# Sheet1.net
KiCad netlist of a schematic drawn in Altium Designer
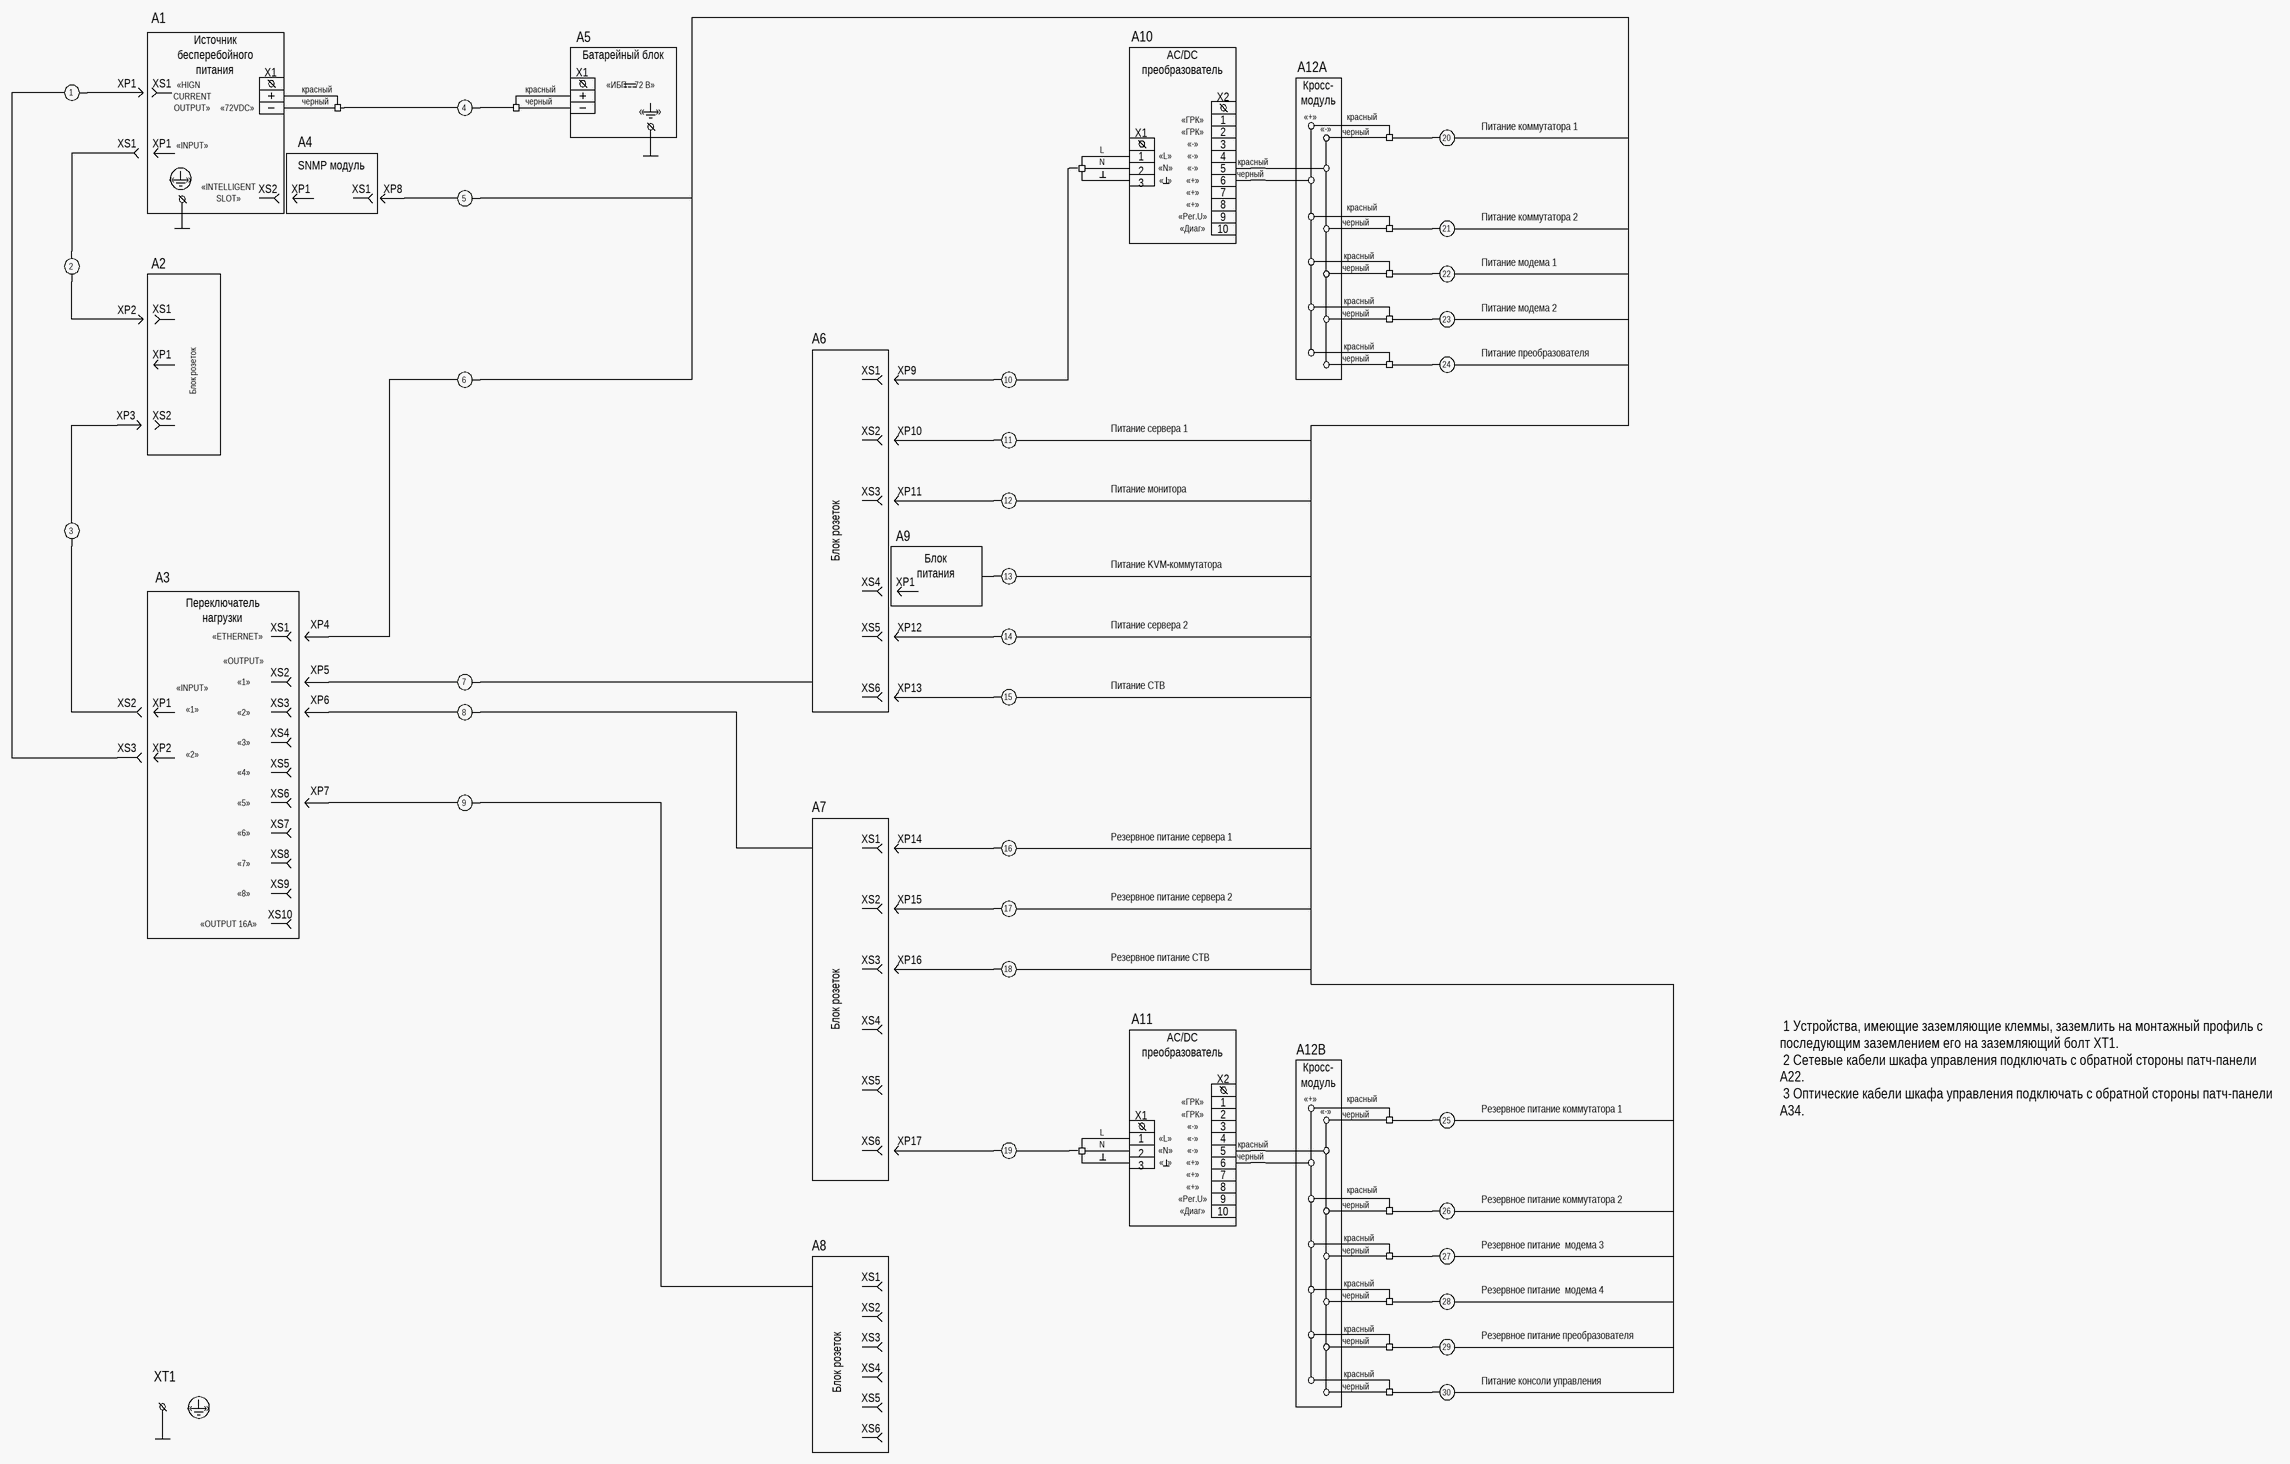
[diagram p0: Sheet1.SchDoc]

(export (version "E")
  (design (tool "Eeschema 10.0.6"))
  (components
    (comp (ref "1") (value "CABLE") (libsource (lib "RSP2STLIB") (part "CABLE")))
    (comp (ref "2") (value "CABLE") (libsource (lib "RSP2STLIB") (part "CABLE")))
    (comp (ref "3") (value "CABLE") (libsource (lib "RSP2STLIB") (part "CABLE")))
    (comp (ref "4") (value "CABLE") (libsource (lib "RSP2STLIB") (part "CABLE")))
    (comp (ref "5") (value "CABLE") (libsource (lib "RSP2STLIB") (part "CABLE")))
    (comp (ref "6") (value "CABLE") (libsource (lib "RSP2STLIB") (part "CABLE")))
    (comp (ref "7") (value "CABLE") (libsource (lib "RSP2STLIB") (part "CABLE")))
    (comp (ref "8") (value "CABLE") (libsource (lib "RSP2STLIB") (part "CABLE")))
    (comp (ref "9") (value "CABLE") (libsource (lib "RSP2STLIB") (part "CABLE")))
    (comp (ref "10") (value "CABLE") (libsource (lib "RSP2STLIB") (part "CABLE")))
    (comp (ref "11") (value "CABLE") (libsource (lib "RSP2STLIB") (part "CABLE")))
    (comp (ref "12") (value "CABLE") (libsource (lib "RSP2STLIB") (part "CABLE")))
    (comp (ref "13") (value "CABLE") (libsource (lib "RSP2STLIB") (part "CABLE")))
    (comp (ref "14") (value "CABLE") (libsource (lib "RSP2STLIB") (part "CABLE")))
    (comp (ref "15") (value "CABLE") (libsource (lib "RSP2STLIB") (part "CABLE")))
    (comp (ref "16") (value "CABLE") (libsource (lib "RSP2STLIB") (part "CABLE")))
    (comp (ref "17") (value "CABLE") (libsource (lib "RSP2STLIB") (part "CABLE")))
    (comp (ref "18") (value "CABLE") (libsource (lib "RSP2STLIB") (part "CABLE")))
    (comp (ref "19") (value "CABLE") (libsource (lib "RSP2STLIB") (part "CABLE")))
    (comp (ref "20") (value "CABLE") (libsource (lib "RSP2STLIB") (part "CABLE")))
    (comp (ref "21") (value "CABLE") (libsource (lib "RSP2STLIB") (part "CABLE")))
    (comp (ref "22") (value "CABLE") (libsource (lib "RSP2STLIB") (part "CABLE")))
    (comp (ref "23") (value "CABLE") (libsource (lib "RSP2STLIB") (part "CABLE")))
    (comp (ref "24") (value "CABLE") (libsource (lib "RSP2STLIB") (part "CABLE")))
    (comp (ref "25") (value "CABLE") (libsource (lib "RSP2STLIB") (part "CABLE")))
    (comp (ref "26") (value "CABLE") (libsource (lib "RSP2STLIB") (part "CABLE")))
    (comp (ref "27") (value "CABLE") (libsource (lib "RSP2STLIB") (part "CABLE")))
    (comp (ref "28") (value "CABLE") (libsource (lib "RSP2STLIB") (part "CABLE")))
    (comp (ref "29") (value "CABLE") (libsource (lib "RSP2STLIB") (part "CABLE")))
    (comp (ref "30") (value "CABLE") (libsource (lib "RSP2STLIB") (part "CABLE")))
    (comp (ref "A1")
      (value "Источник бесперебойного питания SKAT-UPS 3000 RACK Бастион")
      (libsource (lib "RSP2STLIB") (part "Источник бесперебойного питания SKAT-UPS 3000 RACK Бастион"))
    )
    (comp (ref "A2") (value "блок") (libsource (lib "RSP2STLIB") (part "блок")))
    (comp (ref "A3") (value "ПН") (libsource (lib "RSP2STLIB") (part "Переключатель нагрузки")))
    (comp (ref "A4") (value "SNMP_модуль") (libsource (lib "RSP2STLIB") (part "SNMP_модуль")))
    (comp (ref "A5") (value "бб") (libsource (lib "RSP2STLIB") (part "атарейный блок")))
    (comp (ref "A6") (value "БР2") (libsource (lib "RSP2STLIB") (part "блок розеток 2")))
    (comp (ref "A7") (value "БР1") (libsource (lib "RSP2STLIB") (part "блок розеток 1")))
    (comp (ref "A8") (value "БР3") (libsource (lib "RSP2STLIB") (part "блок розеток 3")))
    (comp (ref "A9") (value "блок питания") (libsource (lib "RSP2STLIB") (part "блок питания")))
    (comp (ref "A10") (value "ACDC") (libsource (lib "RSP2STLIB") (part "ACDC преобразователь")))
    (comp (ref "A11") (value "ACDC") (libsource (lib "RSP2STLIB") (part "ACDC преобразователь")))
    (comp (ref "A12") (value "км") (libsource (lib "RSP2STLIB") (part "кросс-модуль")))
    (comp (ref "XP1") (value "XP") (libsource (lib "RSP2STLIB") (part "XP")))
    (comp (ref "XP2") (value "XP") (libsource (lib "RSP2STLIB") (part "XP")))
    (comp (ref "XP3") (value "XP") (libsource (lib "RSP2STLIB") (part "XP")))
    (comp (ref "XP4") (value "XP") (libsource (lib "RSP2STLIB") (part "XP")))
    (comp (ref "XP5") (value "XP") (libsource (lib "RSP2STLIB") (part "XP")))
    (comp (ref "XP6") (value "XP") (libsource (lib "RSP2STLIB") (part "XP")))
    (comp (ref "XP7") (value "XP") (libsource (lib "RSP2STLIB") (part "XP")))
    (comp (ref "XP8") (value "XP") (libsource (lib "RSP2STLIB") (part "XP")))
    (comp (ref "XP9") (value "XP") (libsource (lib "RSP2STLIB") (part "XP")))
    (comp (ref "XP10") (value "XP") (libsource (lib "RSP2STLIB") (part "XP")))
    (comp (ref "XP11") (value "XP") (libsource (lib "RSP2STLIB") (part "XP")))
    (comp (ref "XP12") (value "XP") (libsource (lib "RSP2STLIB") (part "XP")))
    (comp (ref "XP13") (value "XP") (libsource (lib "RSP2STLIB") (part "XP")))
    (comp (ref "XP14") (value "XP") (libsource (lib "RSP2STLIB") (part "XP")))
    (comp (ref "XP15") (value "XP") (libsource (lib "RSP2STLIB") (part "XP")))
    (comp (ref "XP16") (value "XP") (libsource (lib "RSP2STLIB") (part "XP")))
    (comp (ref "XP17") (value "XP") (libsource (lib "RSP2STLIB") (part "XP")))
    (comp (ref "XS1") (value "XS") (libsource (lib "RSP2STLIB") (part "XS")))
    (comp (ref "XS2") (value "XS") (libsource (lib "RSP2STLIB") (part "XS")))
    (comp (ref "XS3") (value "XS") (libsource (lib "RSP2STLIB") (part "XS")))
    (comp (ref "XT1") (value "GND") (libsource (lib "RSP2STLIB") (part "GND")))
  )
  (nets
    (net (code "21") (name "Net-(1-ANAIN2)") (class "Default")
      (node (ref "1") (pin "4") (pinfunction "ANAIN2_4") (pintype "power_in"))
      (node (ref "XS3") (pin "6") (pinfunction "ANAIN4_6") (pintype "power_in"))
    )
    (net (code "22") (name "Net-(1-ANAIN3)") (class "Default")
      (node (ref "1") (pin "5") (pinfunction "ANAIN3_5") (pintype "power_in"))
      (node (ref "XP1") (pin "6") (pinfunction "ANAIN4_6") (pintype "power_in"))
    )
    (net (code "23") (name "Net-(2-ANAIN2)") (class "Default")
      (node (ref "2") (pin "4") (pinfunction "ANAIN2_4") (pintype "power_in"))
      (node (ref "XP2") (pin "6") (pinfunction "ANAIN4_6") (pintype "power_in"))
    )
    (net (code "24") (name "Net-(2-ANAIN3)") (class "Default")
      (node (ref "2") (pin "5") (pinfunction "ANAIN3_5") (pintype "power_in"))
      (node (ref "XS1") (pin "6") (pinfunction "ANAIN4_6") (pintype "power_in"))
    )
    (net (code "25") (name "Net-(3-ANAIN2)") (class "Default")
      (node (ref "3") (pin "4") (pinfunction "ANAIN2_4") (pintype "power_in"))
      (node (ref "XS2") (pin "6") (pinfunction "ANAIN4_6") (pintype "power_in"))
    )
    (net (code "26") (name "Net-(3-ANAIN3)") (class "Default")
      (node (ref "3") (pin "5") (pinfunction "ANAIN3_5") (pintype "power_in"))
      (node (ref "XP3") (pin "6") (pinfunction "ANAIN4_6") (pintype "power_in"))
    )
    (net (code "27") (name "Net-(4-ANAIN2)") (class "Default")
      (node (ref "4") (pin "4") (pinfunction "ANAIN2_4") (pintype "power_in"))
      (node (ref "A1") (pin "6") (pinfunction "ANAIN4_6") (pintype "power_in"))
    )
    (net (code "28") (name "Net-(4-ANAIN3)") (class "Default")
      (node (ref "4") (pin "5") (pinfunction "ANAIN3_5") (pintype "power_in"))
      (node (ref "A5") (pin "6") (pinfunction "ANAIN4_6") (pintype "power_in"))
    )
    (net (code "29") (name "Net-(5-ANAIN2)") (class "Default")
      (node (ref "5") (pin "4") (pinfunction "ANAIN2_4") (pintype "power_in"))
      (node (ref "XP8") (pin "6") (pinfunction "ANAIN4_6") (pintype "power_in"))
    )
    (net (code "30") (name "Net-(6-ANAIN2)") (class "Default")
      (node (ref "6") (pin "4") (pinfunction "ANAIN2_4") (pintype "power_in"))
      (node (ref "XP4") (pin "6") (pinfunction "ANAIN4_6") (pintype "power_in"))
    )
    (net (code "31") (name "Net-(7-ANAIN2)") (class "Default")
      (node (ref "7") (pin "4") (pinfunction "ANAIN2_4") (pintype "power_in"))
      (node (ref "XP5") (pin "6") (pinfunction "ANAIN4_6") (pintype "power_in"))
    )
    (net (code "32") (name "Net-(7-ANAIN3)") (class "Default")
      (node (ref "7") (pin "5") (pinfunction "ANAIN3_5") (pintype "power_in"))
      (node (ref "A6") (pin "5") (pinfunction "ANAIN3_5") (pintype "power_in"))
    )
    (net (code "33") (name "Net-(8-ANAIN2)") (class "Default")
      (node (ref "8") (pin "4") (pinfunction "ANAIN2_4") (pintype "power_in"))
      (node (ref "XP6") (pin "6") (pinfunction "ANAIN4_6") (pintype "power_in"))
    )
    (net (code "34") (name "Net-(8-ANAIN3)") (class "Default")
      (node (ref "8") (pin "5") (pinfunction "ANAIN3_5") (pintype "power_in"))
      (node (ref "A7") (pin "5") (pinfunction "ANAIN3_5") (pintype "power_in"))
    )
    (net (code "35") (name "Net-(9-ANAIN2)") (class "Default")
      (node (ref "9") (pin "4") (pinfunction "ANAIN2_4") (pintype "power_in"))
      (node (ref "XP7") (pin "6") (pinfunction "ANAIN4_6") (pintype "power_in"))
    )
    (net (code "36") (name "Net-(9-ANAIN3)") (class "Default")
      (node (ref "9") (pin "5") (pinfunction "ANAIN3_5") (pintype "power_in"))
      (node (ref "A8") (pin "5") (pinfunction "ANAIN3_5") (pintype "power_in"))
    )
    (net (code "37") (name "Net-(10-ANAIN2)") (class "Default")
      (node (ref "10") (pin "4") (pinfunction "ANAIN2_4") (pintype "power_in"))
      (node (ref "XP9") (pin "6") (pinfunction "ANAIN4_6") (pintype "power_in"))
    )
    (net (code "38") (name "Net-(10-ANAIN3)") (class "Default")
      (node (ref "10") (pin "5") (pinfunction "ANAIN3_5") (pintype "power_in"))
      (node (ref "A10") (pin "5") (pinfunction "ANAIN3_5") (pintype "power_in"))
    )
    (net (code "39") (name "Net-(11-ANAIN2)") (class "Default")
      (node (ref "11") (pin "4") (pinfunction "ANAIN2_4") (pintype "power_in"))
      (node (ref "XP10") (pin "6") (pinfunction "ANAIN4_6") (pintype "power_in"))
    )
    (net (code "40") (name "Net-(12-ANAIN2)") (class "Default")
      (node (ref "12") (pin "4") (pinfunction "ANAIN2_4") (pintype "power_in"))
      (node (ref "XP11") (pin "6") (pinfunction "ANAIN4_6") (pintype "power_in"))
    )
    (net (code "41") (name "Net-(13-ANAIN2)") (class "Default")
      (node (ref "13") (pin "4") (pinfunction "ANAIN2_4") (pintype "power_in"))
      (node (ref "A9") (pin "6") (pinfunction "ANAIN4_6") (pintype "power_in"))
    )
    (net (code "42") (name "Net-(14-ANAIN2)") (class "Default")
      (node (ref "14") (pin "4") (pinfunction "ANAIN2_4") (pintype "power_in"))
      (node (ref "XP12") (pin "6") (pinfunction "ANAIN4_6") (pintype "power_in"))
    )
    (net (code "43") (name "Net-(15-ANAIN2)") (class "Default")
      (node (ref "15") (pin "4") (pinfunction "ANAIN2_4") (pintype "power_in"))
      (node (ref "XP13") (pin "6") (pinfunction "ANAIN4_6") (pintype "power_in"))
    )
    (net (code "44") (name "Net-(16-ANAIN2)") (class "Default")
      (node (ref "16") (pin "4") (pinfunction "ANAIN2_4") (pintype "power_in"))
      (node (ref "XP14") (pin "6") (pinfunction "ANAIN4_6") (pintype "power_in"))
    )
    (net (code "45") (name "Net-(17-ANAIN2)") (class "Default")
      (node (ref "17") (pin "4") (pinfunction "ANAIN2_4") (pintype "power_in"))
      (node (ref "XP15") (pin "6") (pinfunction "ANAIN4_6") (pintype "power_in"))
    )
    (net (code "46") (name "Net-(18-ANAIN2)") (class "Default")
      (node (ref "18") (pin "4") (pinfunction "ANAIN2_4") (pintype "power_in"))
      (node (ref "XP16") (pin "6") (pinfunction "ANAIN4_6") (pintype "power_in"))
    )
    (net (code "47") (name "Net-(19-ANAIN2)") (class "Default")
      (node (ref "19") (pin "4") (pinfunction "ANAIN2_4") (pintype "power_in"))
      (node (ref "XP17") (pin "6") (pinfunction "ANAIN4_6") (pintype "power_in"))
    )
    (net (code "48") (name "Net-(19-ANAIN3)") (class "Default")
      (node (ref "19") (pin "5") (pinfunction "ANAIN3_5") (pintype "power_in"))
      (node (ref "A11") (pin "5") (pinfunction "ANAIN3_5") (pintype "power_in"))
    )
    (net (code "49") (name "Net-(20-ANAIN2)") (class "Default")
      (node (ref "20") (pin "4") (pinfunction "ANAIN2_4") (pintype "power_in"))
      (node (ref "A12") (pin "5") (pinfunction "ANAIN3_5") (pintype "power_in"))
    )
    (net (code "50") (name "Net-(21-ANAIN2)") (class "Default")
      (node (ref "21") (pin "4") (pinfunction "ANAIN2_4") (pintype "power_in"))
      (node (ref "A12") (pin "6") (pinfunction "ANAIN4_6") (pintype "power_in"))
    )
    (net (code "51") (name "Net-(22-ANAIN2)") (class "Default")
      (node (ref "22") (pin "4") (pinfunction "ANAIN2_4") (pintype "power_in"))
      (node (ref "A12") (pin "7") (pinfunction "ANAIN5_7") (pintype "power_in"))
    )
    (net (code "52") (name "Net-(23-ANAIN2)") (class "Default")
      (node (ref "23") (pin "4") (pinfunction "ANAIN2_4") (pintype "power_in"))
      (node (ref "A12") (pin "8") (pinfunction "ANAIN6_8") (pintype "power_in"))
    )
    (net (code "53") (name "Net-(24-ANAIN2)") (class "Default")
      (node (ref "24") (pin "4") (pinfunction "ANAIN2_4") (pintype "power_in"))
      (node (ref "A12") (pin "9") (pinfunction "ANAIN7_9") (pintype "power_in"))
    )
    (net (code "54") (name "Net-(25-ANAIN2)") (class "Default")
      (node (ref "25") (pin "4") (pinfunction "ANAIN2_4") (pintype "power_in"))
      (node (ref "A12") (pin "5") (pinfunction "ANAIN3_5") (pintype "power_in"))
    )
    (net (code "55") (name "Net-(26-ANAIN2)") (class "Default")
      (node (ref "26") (pin "4") (pinfunction "ANAIN2_4") (pintype "power_in"))
      (node (ref "A12") (pin "6") (pinfunction "ANAIN4_6") (pintype "power_in"))
    )
    (net (code "56") (name "Net-(27-ANAIN2)") (class "Default")
      (node (ref "27") (pin "4") (pinfunction "ANAIN2_4") (pintype "power_in"))
      (node (ref "A12") (pin "7") (pinfunction "ANAIN5_7") (pintype "power_in"))
    )
    (net (code "57") (name "Net-(28-ANAIN2)") (class "Default")
      (node (ref "28") (pin "4") (pinfunction "ANAIN2_4") (pintype "power_in"))
      (node (ref "A12") (pin "8") (pinfunction "ANAIN6_8") (pintype "power_in"))
    )
    (net (code "58") (name "Net-(29-ANAIN2)") (class "Default")
      (node (ref "29") (pin "4") (pinfunction "ANAIN2_4") (pintype "power_in"))
      (node (ref "A12") (pin "9") (pinfunction "ANAIN7_9") (pintype "power_in"))
    )
    (net (code "59") (name "Net-(30-ANAIN2)") (class "Default")
      (node (ref "30") (pin "4") (pinfunction "ANAIN2_4") (pintype "power_in"))
      (node (ref "A12") (pin "10") (pinfunction "ANAIN8_10") (pintype "power_in"))
    )
    (net (code "60") (name "Net-(A10-ANAIN4)") (class "Default")
      (node (ref "A10") (pin "6") (pinfunction "ANAIN4_6") (pintype "power_in"))
      (node (ref "A12") (pin "8") (pinfunction "ANAIN6_8") (pintype "power_in"))
    )
    (net (code "61") (name "Net-(A10-ANAIN5)") (class "Default")
      (node (ref "A10") (pin "7") (pinfunction "ANAIN5_7") (pintype "power_in"))
      (node (ref "A12") (pin "7") (pinfunction "ANAIN5_7") (pintype "power_in"))
    )
    (net (code "62") (name "Net-(A11-ANAIN4)") (class "Default")
      (node (ref "A11") (pin "6") (pinfunction "ANAIN4_6") (pintype "power_in"))
      (node (ref "A12") (pin "8") (pinfunction "ANAIN6_8") (pintype "power_in"))
    )
    (net (code "63") (name "Net-(A11-ANAIN5)") (class "Default")
      (node (ref "A11") (pin "7") (pinfunction "ANAIN5_7") (pintype "power_in"))
      (node (ref "A12") (pin "7") (pinfunction "ANAIN5_7") (pintype "power_in"))
    )
    (net (code "64") (name "unconnected-(5-ANAIN3-Pad5)") (class "Default")
      (node (ref "5") (pin "5") (pinfunction "ANAIN3_5") (pintype "power_in"))
    )
    (net (code "65") (name "unconnected-(6-ANAIN3-Pad5)") (class "Default")
      (node (ref "6") (pin "5") (pinfunction "ANAIN3_5") (pintype "power_in"))
    )
    (net (code "66") (name "unconnected-(11-ANAIN3-Pad5)") (class "Default")
      (node (ref "11") (pin "5") (pinfunction "ANAIN3_5") (pintype "power_in"))
    )
    (net (code "67") (name "unconnected-(12-ANAIN3-Pad5)") (class "Default")
      (node (ref "12") (pin "5") (pinfunction "ANAIN3_5") (pintype "power_in"))
    )
    (net (code "68") (name "unconnected-(13-ANAIN3-Pad5)") (class "Default")
      (node (ref "13") (pin "5") (pinfunction "ANAIN3_5") (pintype "power_in"))
    )
    (net (code "69") (name "unconnected-(14-ANAIN3-Pad5)") (class "Default")
      (node (ref "14") (pin "5") (pinfunction "ANAIN3_5") (pintype "power_in"))
    )
    (net (code "70") (name "unconnected-(15-ANAIN3-Pad5)") (class "Default")
      (node (ref "15") (pin "5") (pinfunction "ANAIN3_5") (pintype "power_in"))
    )
    (net (code "71") (name "unconnected-(16-ANAIN3-Pad5)") (class "Default")
      (node (ref "16") (pin "5") (pinfunction "ANAIN3_5") (pintype "power_in"))
    )
    (net (code "72") (name "unconnected-(17-ANAIN3-Pad5)") (class "Default")
      (node (ref "17") (pin "5") (pinfunction "ANAIN3_5") (pintype "power_in"))
    )
    (net (code "73") (name "unconnected-(18-ANAIN3-Pad5)") (class "Default")
      (node (ref "18") (pin "5") (pinfunction "ANAIN3_5") (pintype "power_in"))
    )
    (net (code "74") (name "unconnected-(20-ANAIN3-Pad5)") (class "Default")
      (node (ref "20") (pin "5") (pinfunction "ANAIN3_5") (pintype "power_in"))
    )
    (net (code "75") (name "unconnected-(21-ANAIN3-Pad5)") (class "Default")
      (node (ref "21") (pin "5") (pinfunction "ANAIN3_5") (pintype "power_in"))
    )
    (net (code "76") (name "unconnected-(22-ANAIN3-Pad5)") (class "Default")
      (node (ref "22") (pin "5") (pinfunction "ANAIN3_5") (pintype "power_in"))
    )
    (net (code "77") (name "unconnected-(23-ANAIN3-Pad5)") (class "Default")
      (node (ref "23") (pin "5") (pinfunction "ANAIN3_5") (pintype "power_in"))
    )
    (net (code "78") (name "unconnected-(24-ANAIN3-Pad5)") (class "Default")
      (node (ref "24") (pin "5") (pinfunction "ANAIN3_5") (pintype "power_in"))
    )
    (net (code "79") (name "unconnected-(25-ANAIN3-Pad5)") (class "Default")
      (node (ref "25") (pin "5") (pinfunction "ANAIN3_5") (pintype "power_in"))
    )
    (net (code "80") (name "unconnected-(26-ANAIN3-Pad5)") (class "Default")
      (node (ref "26") (pin "5") (pinfunction "ANAIN3_5") (pintype "power_in"))
    )
    (net (code "81") (name "unconnected-(27-ANAIN3-Pad5)") (class "Default")
      (node (ref "27") (pin "5") (pinfunction "ANAIN3_5") (pintype "power_in"))
    )
    (net (code "82") (name "unconnected-(28-ANAIN3-Pad5)") (class "Default")
      (node (ref "28") (pin "5") (pinfunction "ANAIN3_5") (pintype "power_in"))
    )
    (net (code "83") (name "unconnected-(29-ANAIN3-Pad5)") (class "Default")
      (node (ref "29") (pin "5") (pinfunction "ANAIN3_5") (pintype "power_in"))
    )
    (net (code "84") (name "unconnected-(30-ANAIN3-Pad5)") (class "Default")
      (node (ref "30") (pin "5") (pinfunction "ANAIN3_5") (pintype "power_in"))
    )
  )
)
